# Indication_and_Notification.net
KiCad netlist of a schematic drawn in Altium Designer
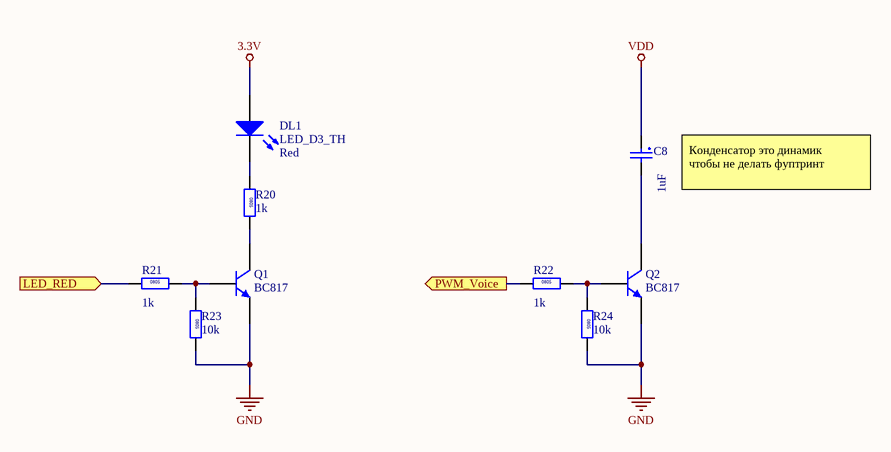
[diagram p0: Indication_and_Notification.SchDoc]

(export (version "E")
  (design (tool "Eeschema 10.0.6"))
  (components
    (comp (ref "C8")
      (value "1uF")
      (footprint "ECAP1325")
      (description "Capacitor electrolytic 5 mm pitch, 13*25 body")
      (fields (field (name "Comment") "ECAP-1325"))
      (libsource (lib "Passive") (part "ECAP-1325"))
    )
    (comp (ref "DL1")
      (value "LED_D3_TH")
      (footprint "LED_D3_TH")
      (description "LED Through hole D3mm")
      (fields (field (name "ALTIUM_VALUE") "Red"))
      (libsource (lib "Discrete") (part "LED_D3_TH"))
    )
    (comp (ref "Q1")
      (value "BC817")
      (footprint "SOT23-3M")
      (description "BC817 NPN Transistor")
      (libsource (lib "Discrete") (part "BC817"))
    )
    (comp (ref "Q2")
      (value "BC817")
      (footprint "SOT23-3M")
      (description "BC817 NPN Transistor")
      (libsource (lib "Discrete") (part "BC817"))
    )
    (comp (ref "R20")
      (value "1k")
      (footprint "RESC2012-0805M")
      (description "Resistor 0805")
      (fields (field (name "Comment") "RESC_0805_R"))
      (libsource (lib "Passive") (part "RESC_0805_R"))
    )
    (comp (ref "R21")
      (value "1k")
      (footprint "RESC2012-0805M")
      (description "Resistor 0805")
      (fields (field (name "Comment") "RESC_0805_R"))
      (libsource (lib "") (part "RESC_0805_R_1"))
    )
    (comp (ref "R22")
      (value "1k")
      (footprint "RESC2012-0805M")
      (description "Resistor 0805")
      (fields (field (name "Comment") "RESC_0805_R"))
      (libsource (lib "") (part "RESC_0805_R_1"))
    )
    (comp (ref "R23")
      (value "10k")
      (footprint "RESC2012-0805M")
      (description "Resistor 0805")
      (fields (field (name "Comment") "RESC_0805_R"))
      (libsource (lib "Passive") (part "RESC_0805_R"))
    )
    (comp (ref "R24")
      (value "10k")
      (footprint "RESC2012-0805M")
      (description "Resistor 0805")
      (fields (field (name "Comment") "RESC_0805_R"))
      (libsource (lib "Passive") (part "RESC_0805_R"))
    )
  )
  (nets
    (net (code "1") (name "/LED_RED") (class "Default")
      (node (ref "R21") (pin "1") (pinfunction "1_1") (pintype "passive"))
    )
    (net (code "2") (name "/PWM_Voice") (class "Default")
      (node (ref "R22") (pin "1") (pinfunction "1_1") (pintype "passive"))
    )
    (net (code "3") (name "3.3V") (class "Default")
      (node (ref "DL1") (pin "1") (pinfunction "A_1") (pintype "passive"))
    )
    (net (code "4") (name "GND") (class "Default")
      (node (ref "Q1") (pin "2") (pinfunction "E_2") (pintype "passive"))
      (node (ref "Q2") (pin "2") (pinfunction "E_2") (pintype "passive"))
      (node (ref "R23") (pin "2") (pinfunction "2_2") (pintype "passive"))
      (node (ref "R24") (pin "2") (pinfunction "2_2") (pintype "passive"))
    )
    (net (code "5") (name "Net-(DL1-K)") (class "Default")
      (node (ref "DL1") (pin "2") (pinfunction "K_2") (pintype "passive"))
      (node (ref "R20") (pin "1") (pinfunction "1_1") (pintype "passive"))
    )
    (net (code "6") (name "Net-(Q1-B)") (class "Default")
      (node (ref "Q1") (pin "1") (pinfunction "B_1") (pintype "passive"))
      (node (ref "R21") (pin "2") (pinfunction "2_2") (pintype "passive"))
      (node (ref "R23") (pin "1") (pinfunction "1_1") (pintype "passive"))
    )
    (net (code "7") (name "Net-(Q1-C)") (class "Default")
      (node (ref "Q1") (pin "3") (pinfunction "C_3") (pintype "passive"))
      (node (ref "R20") (pin "2") (pinfunction "2_2") (pintype "passive"))
    )
    (net (code "8") (name "Net-(Q2-B)") (class "Default")
      (node (ref "Q2") (pin "1") (pinfunction "B_1") (pintype "passive"))
      (node (ref "R22") (pin "2") (pinfunction "2_2") (pintype "passive"))
      (node (ref "R24") (pin "1") (pinfunction "1_1") (pintype "passive"))
    )
    (net (code "9") (name "Net-(Q2-C)") (class "Default")
      (node (ref "C8") (pin "2") (pinfunction "2_2") (pintype "passive"))
      (node (ref "Q2") (pin "3") (pinfunction "C_3") (pintype "passive"))
    )
    (net (code "10") (name "VDD") (class "Default")
      (node (ref "C8") (pin "1") (pinfunction "1_1") (pintype "passive"))
    )
  )
)
